# 06_-_GPIO.net
KiCad netlist of a schematic drawn in Altium Designer
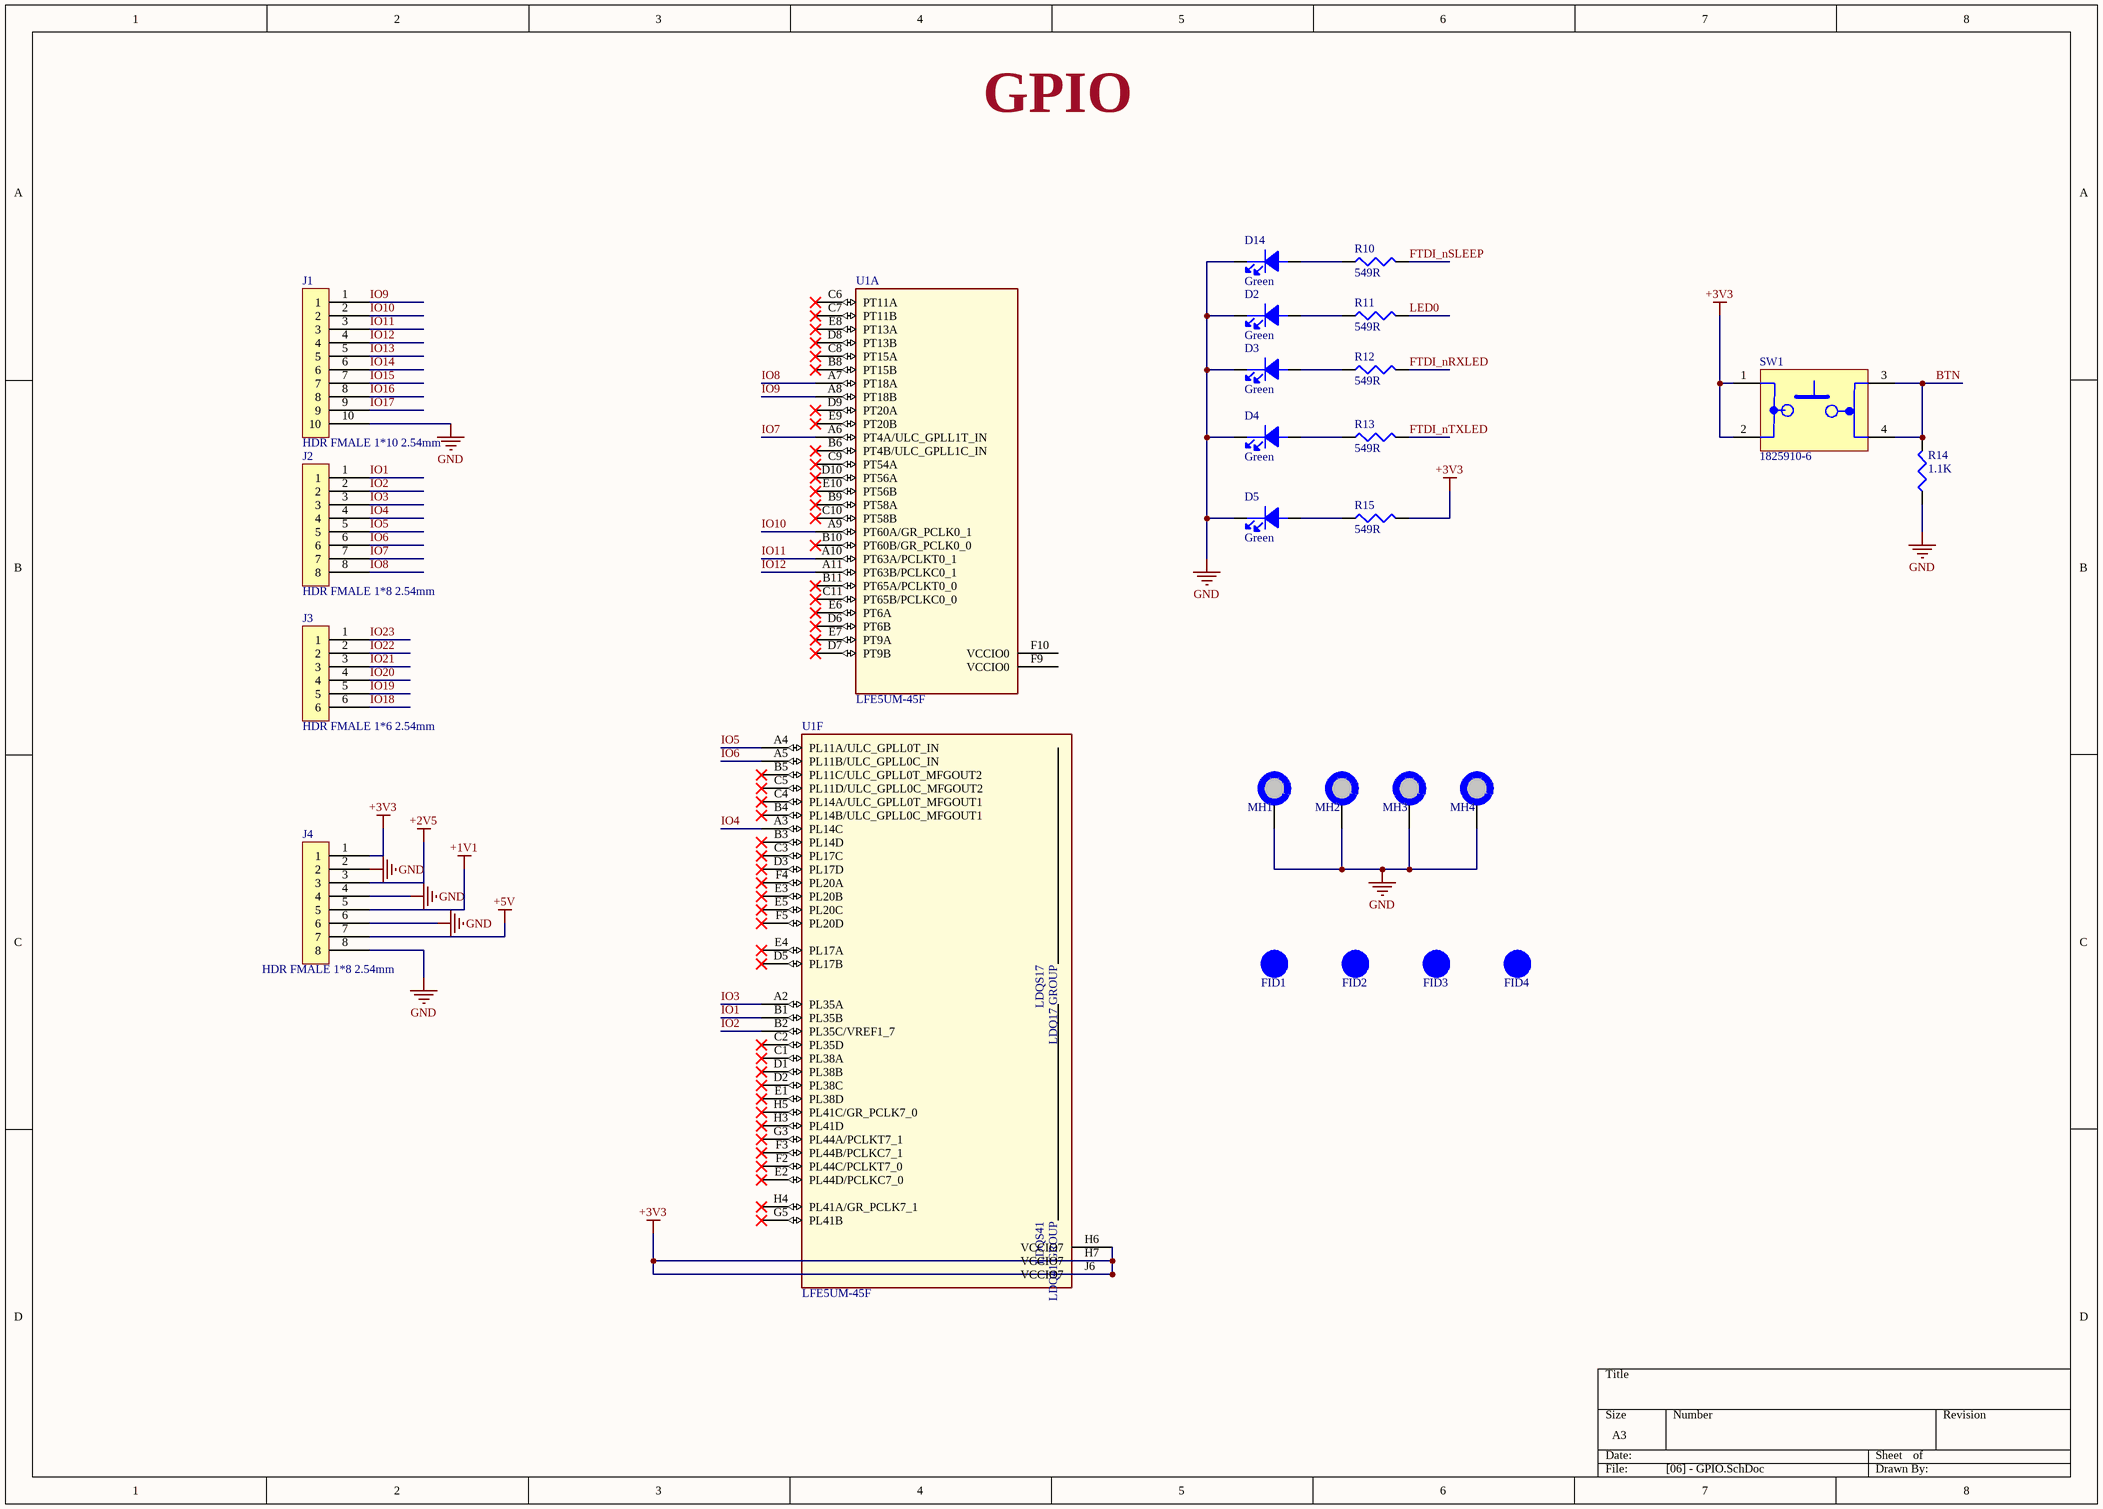
[diagram p0: [06] - GPIO.SchDoc]

(export (version "E")
  (design (tool "Eeschema 10.0.6"))
  (components
    (comp (ref "D2")
      (value "Green")
      (footprint "LED_0603")
      (description "LED Uni-Color Green 572nm 2-Pin Chip 0603(1608Metric) T/R")
      (fields
        (field (name "MANUFACTURER") "Osram Opto")
        (field (name "MANUFACTURER PART NUMBER") "LGL29K-G2J1-24-Z")
      )
      (libsource (lib "ECP5_V2") (part "LGL29K-G2J1-24-Z"))
    )
    (comp (ref "D3")
      (value "Green")
      (footprint "LED_0603")
      (description "LED Uni-Color Green 572nm 2-Pin Chip 0603(1608Metric) T/R")
      (fields
        (field (name "MANUFACTURER") "Osram Opto")
        (field (name "MANUFACTURER PART NUMBER") "LGL29K-G2J1-24-Z")
      )
      (libsource (lib "ECP5_V2") (part "LGL29K-G2J1-24-Z"))
    )
    (comp (ref "D4")
      (value "Green")
      (footprint "LED_0603")
      (description "LED Uni-Color Green 572nm 2-Pin Chip 0603(1608Metric) T/R")
      (fields
        (field (name "MANUFACTURER") "Osram Opto")
        (field (name "MANUFACTURER PART NUMBER") "LGL29K-G2J1-24-Z")
      )
      (libsource (lib "ECP5_V2") (part "LGL29K-G2J1-24-Z"))
    )
    (comp (ref "D5")
      (value "Green")
      (footprint "LED_0603")
      (description "LED Uni-Color Green 572nm 2-Pin Chip 0603(1608Metric) T/R")
      (fields
        (field (name "MANUFACTURER") "Osram Opto")
        (field (name "MANUFACTURER PART NUMBER") "LGL29K-G2J1-24-Z")
      )
      (libsource (lib "ECP5_V2") (part "LGL29K-G2J1-24-Z"))
    )
    (comp (ref "D14")
      (value "Green")
      (footprint "LED_0603")
      (description "LED Uni-Color Green 572nm 2-Pin Chip 0603(1608Metric) T/R")
      (fields
        (field (name "MANUFACTURER") "Osram Opto")
        (field (name "MANUFACTURER PART NUMBER") "LGL29K-G2J1-24-Z")
      )
      (libsource (lib "ECP5_V2") (part "LGL29K-G2J1-24-Z"))
    )
    (comp (ref "FID1")
      (value "FID_1MMC")
      (footprint "FID_40x120D")
      (description "Fiducial 40mil Diameter 120mil Mask")
      (libsource (lib "ECP5_V2") (part "FID_1MMC"))
    )
    (comp (ref "FID2")
      (value "FID_1MMC")
      (footprint "FID_40x120D")
      (description "Fiducial 40mil Diameter 120mil Mask")
      (libsource (lib "ECP5_V2") (part "FID_1MMC"))
    )
    (comp (ref "FID3")
      (value "FID_1MMC")
      (footprint "FID_40x120D")
      (description "Fiducial 40mil Diameter 120mil Mask")
      (libsource (lib "ECP5_V2") (part "FID_1MMC"))
    )
    (comp (ref "FID4")
      (value "FID_1MMC")
      (footprint "FID_40x120D")
      (description "Fiducial 40mil Diameter 120mil Mask")
      (libsource (lib "ECP5_V2") (part "FID_1MMC"))
    )
    (comp (ref "J1")
      (value "HDR FMALE 1*10 2.54mm")
      (footprint "Hdr_Female_1*10_2.54mm")
      (description "10-WAY SIL VERT SOCKET L/FREE")
      (fields (field (name "MANUFACTURER") "Harwin") (field (name "MANUFACTURER PART NUMBER") "M20-7821046"))
      (libsource (lib "ECP5_V2") (part "M20-7821046"))
    )
    (comp (ref "J2")
      (value "HDR FMALE 1*8 2.54mm")
      (footprint "Hdr_Female_1*8_2.54mm")
      (description "08-WAY SIL VERT SOCKET L/FREE")
      (fields (field (name "MANUFACTURER") "Harwin") (field (name "MANUFACTURER PART NUMBER") "M20-7820842"))
      (libsource (lib "ECP5_V2") (part "M20-7820842"))
    )
    (comp (ref "J3")
      (value "HDR FMALE 1*6 2.54mm")
      (footprint "Hdr_Female_1*6_2.54mm")
      (description "06-WAY SIL VERT SOCKET L/FREE")
      (fields (field (name "MANUFACTURER") "Harwin") (field (name "MANUFACTURER PART NUMBER") "M20-7820646"))
      (libsource (lib "ECP5_V2") (part "M20-7820646"))
    )
    (comp (ref "J4")
      (value "HDR FMALE 1*8 2.54mm")
      (footprint "Hdr_Female_1*8_2.54mm")
      (description "08-WAY SIL VERT SOCKET L/FREE")
      (fields (field (name "MANUFACTURER") "Harwin") (field (name "MANUFACTURER PART NUMBER") "M20-7820842"))
      (libsource (lib "ECP5_V2") (part "M20-7820842"))
    )
    (comp (ref "MH1")
      (value "MH_7.4MMC_3.2MMD")
      (footprint "MH_7.4MMC_3.2MMD")
      (description "Mounting Hole 7..4mm Diameter_3.2mm Drill")
      (libsource (lib "ECP5_V2") (part "MH_7.4MMC_3.2MMD"))
    )
    (comp (ref "MH2")
      (value "MH_7.4MMC_3.2MMD")
      (footprint "MH_7.4MMC_3.2MMD")
      (description "Mounting Hole 7..4mm Diameter_3.2mm Drill")
      (libsource (lib "ECP5_V2") (part "MH_7.4MMC_3.2MMD"))
    )
    (comp (ref "MH3")
      (value "MH_7.4MMC_3.2MMD")
      (footprint "MH_7.4MMC_3.2MMD")
      (description "Mounting Hole 7..4mm Diameter_3.2mm Drill")
      (libsource (lib "ECP5_V2") (part "MH_7.4MMC_3.2MMD"))
    )
    (comp (ref "MH4")
      (value "MH_7.4MMC_3.2MMD")
      (footprint "MH_7.4MMC_3.2MMD")
      (description "Mounting Hole 7..4mm Diameter_3.2mm Drill")
      (libsource (lib "ECP5_V2") (part "MH_7.4MMC_3.2MMD"))
    )
    (comp (ref "R10")
      (value "549R")
      (footprint "R0603")
      (description "RES SMD 549 OHM 1% 1/10W 0603")
      (fields
        (field (name "MANUFACTURER") "Yageo")
        (field (name "MANUFACTURER PART NUMBER") "RC0603FR-07549RL")
      )
      (libsource (lib "ECP5_V2") (part "RC0603FR-07549RL"))
    )
    (comp (ref "R11")
      (value "549R")
      (footprint "R0603")
      (description "RES SMD 549 OHM 1% 1/10W 0603")
      (fields
        (field (name "MANUFACTURER") "Yageo")
        (field (name "MANUFACTURER PART NUMBER") "RC0603FR-07549RL")
      )
      (libsource (lib "ECP5_V2") (part "RC0603FR-07549RL"))
    )
    (comp (ref "R12")
      (value "549R")
      (footprint "R0603")
      (description "RES SMD 549 OHM 1% 1/10W 0603")
      (fields
        (field (name "MANUFACTURER") "Yageo")
        (field (name "MANUFACTURER PART NUMBER") "RC0603FR-07549RL")
      )
      (libsource (lib "ECP5_V2") (part "RC0603FR-07549RL"))
    )
    (comp (ref "R13")
      (value "549R")
      (footprint "R0603")
      (description "RES SMD 549 OHM 1% 1/10W 0603")
      (fields
        (field (name "MANUFACTURER") "Yageo")
        (field (name "MANUFACTURER PART NUMBER") "RC0603FR-07549RL")
      )
      (libsource (lib "ECP5_V2") (part "RC0603FR-07549RL"))
    )
    (comp (ref "R14")
      (value "1.1K")
      (footprint "R0603")
      (description "RES SMD 1.1K OHM 1% 1/10W 0603")
      (fields
        (field (name "MANUFACTURER") "Yageo")
        (field (name "MANUFACTURER PART NUMBER") "RC0603FR-071K1L")
      )
      (libsource (lib "ECP5_V2") (part "RC0603FR-071K1L"))
    )
    (comp (ref "R15")
      (value "549R")
      (footprint "R0603")
      (description "RES SMD 549 OHM 1% 1/10W 0603")
      (fields
        (field (name "MANUFACTURER") "Yageo")
        (field (name "MANUFACTURER PART NUMBER") "RC0603FR-07549RL")
      )
      (libsource (lib "ECP5_V2") (part "RC0603FR-07549RL"))
    )
    (comp (ref "SW1")
      (value "1825910-6")
      (footprint "1825910-6")
      (description "ALCOSWITCH - TE CONNECTIVITY - 1825910-6 - TACT SWITCH, SPST, 0.05A, 24VDC, SOLDER")
      (fields (field (name "MANUFACTURER") "TE Connectivity Alcoswitch"))
      (libsource (lib "ECP5_V2") (part "1825910-6"))
    )
    (comp (ref "U1")
      (value "LFE5UM-45F")
      (footprint "LFE5BG381")
      (description "ECP5 Series 44 K LUTs 203 I/O 1.1 V Slow Surface Mount FPGA - CABGA-381")
      (fields
        (field (name "MANUFACTURER") "Lattice Semiconductor")
        (field (name "MANUFACTURER PART NUMBER") "LFE5UM-45F-6BG381C")
      )
      (libsource (lib "ECP5_V2") (part "LFE5UM-45F-6BG381C"))
    )
  )
  (nets
    (net (code "1") (name "+1V1") (class "Default")
      (node (ref "J4") (pin "5") (pinfunction "5_5") (pintype "passive"))
    )
    (net (code "2") (name "+2V5") (class "Default")
      (node (ref "J4") (pin "3") (pinfunction "3_3") (pintype "passive"))
    )
    (net (code "3") (name "+3V3") (class "Default")
      (node (ref "J4") (pin "1") (pinfunction "1_1") (pintype "passive"))
      (node (ref "R15") (pin "2") (pinfunction "2_2") (pintype "passive"))
      (node (ref "SW1") (pin "1") (pintype "passive"))
      (node (ref "SW1") (pin "2") (pintype "passive"))
      (node (ref "U1") (pin "H6") (pinfunction "VCCIO7_H6") (pintype "power_in"))
      (node (ref "U1") (pin "H7") (pinfunction "VCCIO7_H7") (pintype "power_in"))
      (node (ref "U1") (pin "J6") (pinfunction "VCCIO7_J6") (pintype "power_in"))
    )
    (net (code "4") (name "+5V") (class "Default")
      (node (ref "J4") (pin "7") (pinfunction "7_7") (pintype "passive"))
    )
    (net (code "5") (name "/BTN") (class "Default")
      (node (ref "R14") (pin "2") (pinfunction "2_2") (pintype "passive"))
      (node (ref "SW1") (pin "3") (pintype "passive"))
      (node (ref "SW1") (pin "4") (pintype "passive"))
    )
    (net (code "6") (name "/FTDI_nRXLED") (class "Default")
      (node (ref "R12") (pin "2") (pinfunction "2_2") (pintype "passive"))
    )
    (net (code "7") (name "/FTDI_nSLEEP") (class "Default")
      (node (ref "R10") (pin "2") (pinfunction "2_2") (pintype "passive"))
    )
    (net (code "8") (name "/FTDI_nTXLED") (class "Default")
      (node (ref "R13") (pin "2") (pinfunction "2_2") (pintype "passive"))
    )
    (net (code "9") (name "/IO1") (class "Default")
      (node (ref "J2") (pin "1") (pinfunction "1_1") (pintype "passive"))
      (node (ref "U1") (pin "B1") (pinfunction "PL35B_B1") (pintype "bidirectional"))
    )
    (net (code "10") (name "/IO2") (class "Default")
      (node (ref "J2") (pin "2") (pinfunction "2_2") (pintype "passive"))
      (node (ref "U1") (pin "B2") (pinfunction "PL35C/VREF1_7_B2") (pintype "bidirectional"))
    )
    (net (code "11") (name "/IO3") (class "Default")
      (node (ref "J2") (pin "3") (pinfunction "3_3") (pintype "passive"))
      (node (ref "U1") (pin "A2") (pinfunction "PL35A_A2") (pintype "bidirectional"))
    )
    (net (code "12") (name "/IO4") (class "Default")
      (node (ref "J2") (pin "4") (pinfunction "4_4") (pintype "passive"))
      (node (ref "U1") (pin "A3") (pinfunction "PL14C_A3") (pintype "bidirectional"))
    )
    (net (code "13") (name "/IO5") (class "Default")
      (node (ref "J2") (pin "5") (pinfunction "5_5") (pintype "passive"))
      (node (ref "U1") (pin "A4") (pinfunction "PL11A/ULC_GPLL0T_IN_A4") (pintype "bidirectional"))
    )
    (net (code "14") (name "/IO6") (class "Default")
      (node (ref "J2") (pin "6") (pinfunction "6_6") (pintype "passive"))
      (node (ref "U1") (pin "A5") (pinfunction "PL11B/ULC_GPLL0C_IN_A5") (pintype "bidirectional"))
    )
    (net (code "15") (name "/IO7") (class "Default")
      (node (ref "J2") (pin "7") (pinfunction "7_7") (pintype "passive"))
      (node (ref "U1") (pin "A6") (pinfunction "PT4A/ULC_GPLL1T_IN_A6") (pintype "bidirectional"))
    )
    (net (code "16") (name "/IO8") (class "Default")
      (node (ref "J2") (pin "8") (pinfunction "8_8") (pintype "passive"))
      (node (ref "U1") (pin "A7") (pinfunction "PT18A_A7") (pintype "bidirectional"))
    )
    (net (code "17") (name "/IO9") (class "Default")
      (node (ref "J1") (pin "1") (pinfunction "1_1") (pintype "passive"))
      (node (ref "U1") (pin "A8") (pinfunction "PT18B_A8") (pintype "bidirectional"))
    )
    (net (code "18") (name "/IO10") (class "Default")
      (node (ref "J1") (pin "2") (pinfunction "2_2") (pintype "passive"))
      (node (ref "U1") (pin "A9") (pinfunction "PT60A/GR_PCLK0_1_A9") (pintype "bidirectional"))
    )
    (net (code "19") (name "/IO11") (class "Default")
      (node (ref "J1") (pin "3") (pinfunction "3_3") (pintype "passive"))
      (node (ref "U1") (pin "A10") (pinfunction "PT63A/PCLKT0_1_A10") (pintype "bidirectional"))
    )
    (net (code "20") (name "/IO12") (class "Default")
      (node (ref "J1") (pin "4") (pinfunction "4_4") (pintype "passive"))
      (node (ref "U1") (pin "A11") (pinfunction "PT63B/PCLKC0_1_A11") (pintype "bidirectional"))
    )
    (net (code "21") (name "/IO13") (class "Default")
      (node (ref "J1") (pin "5") (pinfunction "5_5") (pintype "passive"))
    )
    (net (code "22") (name "/IO14") (class "Default")
      (node (ref "J1") (pin "6") (pinfunction "6_6") (pintype "passive"))
    )
    (net (code "23") (name "/IO15") (class "Default")
      (node (ref "J1") (pin "7") (pinfunction "7_7") (pintype "passive"))
    )
    (net (code "24") (name "/IO16") (class "Default")
      (node (ref "J1") (pin "8") (pinfunction "8_8") (pintype "passive"))
    )
    (net (code "25") (name "/IO17") (class "Default")
      (node (ref "J1") (pin "9") (pinfunction "9_9") (pintype "passive"))
    )
    (net (code "26") (name "/IO18") (class "Default")
      (node (ref "J3") (pin "6") (pinfunction "6_6") (pintype "passive"))
    )
    (net (code "27") (name "/IO19") (class "Default")
      (node (ref "J3") (pin "5") (pinfunction "5_5") (pintype "passive"))
    )
    (net (code "28") (name "/IO20") (class "Default")
      (node (ref "J3") (pin "4") (pinfunction "4_4") (pintype "passive"))
    )
    (net (code "29") (name "/IO21") (class "Default")
      (node (ref "J3") (pin "3") (pinfunction "3_3") (pintype "passive"))
    )
    (net (code "30") (name "/IO22") (class "Default")
      (node (ref "J3") (pin "2") (pinfunction "2_2") (pintype "passive"))
    )
    (net (code "31") (name "/IO23") (class "Default")
      (node (ref "J3") (pin "1") (pinfunction "1_1") (pintype "passive"))
    )
    (net (code "32") (name "/LED0") (class "Default")
      (node (ref "R11") (pin "2") (pinfunction "2_2") (pintype "passive"))
    )
    (net (code "33") (name "GND") (class "Default")
      (node (ref "D14") (pin "1") (pinfunction "Cathode_1") (pintype "passive"))
      (node (ref "D2") (pin "1") (pinfunction "Cathode_1") (pintype "passive"))
      (node (ref "D3") (pin "1") (pinfunction "Cathode_1") (pintype "passive"))
      (node (ref "D4") (pin "1") (pinfunction "Cathode_1") (pintype "passive"))
      (node (ref "D5") (pin "1") (pinfunction "Cathode_1") (pintype "passive"))
      (node (ref "J1") (pin "10") (pinfunction "10_10") (pintype "passive"))
      (node (ref "J4") (pin "2") (pinfunction "2_2") (pintype "passive"))
      (node (ref "J4") (pin "4") (pinfunction "4_4") (pintype "passive"))
      (node (ref "J4") (pin "6") (pinfunction "6_6") (pintype "passive"))
      (node (ref "J4") (pin "8") (pinfunction "8_8") (pintype "passive"))
      (node (ref "MH1") (pin "1") (pinfunction "1_1") (pintype "passive"))
      (node (ref "MH2") (pin "1") (pinfunction "1_1") (pintype "passive"))
      (node (ref "MH3") (pin "1") (pinfunction "1_1") (pintype "passive"))
      (node (ref "MH4") (pin "1") (pinfunction "1_1") (pintype "passive"))
      (node (ref "R14") (pin "1") (pinfunction "1_1") (pintype "passive"))
    )
    (net (code "34") (name "Net-(D2-Anode)") (class "Default")
      (node (ref "D2") (pin "2") (pinfunction "Anode_2") (pintype "passive"))
      (node (ref "R11") (pin "1") (pinfunction "1_1") (pintype "passive"))
    )
    (net (code "35") (name "Net-(D3-Anode)") (class "Default")
      (node (ref "D3") (pin "2") (pinfunction "Anode_2") (pintype "passive"))
      (node (ref "R12") (pin "1") (pinfunction "1_1") (pintype "passive"))
    )
    (net (code "36") (name "Net-(D4-Anode)") (class "Default")
      (node (ref "D4") (pin "2") (pinfunction "Anode_2") (pintype "passive"))
      (node (ref "R13") (pin "1") (pinfunction "1_1") (pintype "passive"))
    )
    (net (code "37") (name "Net-(D5-Anode)") (class "Default")
      (node (ref "D5") (pin "2") (pinfunction "Anode_2") (pintype "passive"))
      (node (ref "R15") (pin "1") (pinfunction "1_1") (pintype "passive"))
    )
    (net (code "38") (name "Net-(D14-Anode)") (class "Default")
      (node (ref "D14") (pin "2") (pinfunction "Anode_2") (pintype "passive"))
      (node (ref "R10") (pin "1") (pinfunction "1_1") (pintype "passive"))
    )
    (net (code "39") (name "unconnected-(U1A-PT4B{slash}ULC_GPLL1C_IN-PadB6)") (class "Default")
      (node (ref "U1") (pin "B6") (pinfunction "PT4B/ULC_GPLL1C_IN_B6") (pintype "bidirectional+no_connect"))
    )
    (net (code "40") (name "unconnected-(U1A-PT6A-PadE6)") (class "Default")
      (node (ref "U1") (pin "E6") (pinfunction "PT6A_E6") (pintype "bidirectional+no_connect"))
    )
    (net (code "41") (name "unconnected-(U1A-PT6B-PadD6)") (class "Default")
      (node (ref "U1") (pin "D6") (pinfunction "PT6B_D6") (pintype "bidirectional+no_connect"))
    )
    (net (code "42") (name "unconnected-(U1A-PT9A-PadE7)") (class "Default")
      (node (ref "U1") (pin "E7") (pinfunction "PT9A_E7") (pintype "bidirectional+no_connect"))
    )
    (net (code "43") (name "unconnected-(U1A-PT9B-PadD7)") (class "Default")
      (node (ref "U1") (pin "D7") (pinfunction "PT9B_D7") (pintype "bidirectional+no_connect"))
    )
    (net (code "44") (name "unconnected-(U1A-PT11A-PadC6)") (class "Default")
      (node (ref "U1") (pin "C6") (pinfunction "PT11A_C6") (pintype "bidirectional+no_connect"))
    )
    (net (code "45") (name "unconnected-(U1A-PT11B-PadC7)") (class "Default")
      (node (ref "U1") (pin "C7") (pinfunction "PT11B_C7") (pintype "bidirectional+no_connect"))
    )
    (net (code "46") (name "unconnected-(U1A-PT13A-PadE8)") (class "Default")
      (node (ref "U1") (pin "E8") (pinfunction "PT13A_E8") (pintype "bidirectional+no_connect"))
    )
    (net (code "47") (name "unconnected-(U1A-PT13B-PadD8)") (class "Default")
      (node (ref "U1") (pin "D8") (pinfunction "PT13B_D8") (pintype "bidirectional+no_connect"))
    )
    (net (code "48") (name "unconnected-(U1A-PT15A-PadC8)") (class "Default")
      (node (ref "U1") (pin "C8") (pinfunction "PT15A_C8") (pintype "bidirectional+no_connect"))
    )
    (net (code "49") (name "unconnected-(U1A-PT15B-PadB8)") (class "Default")
      (node (ref "U1") (pin "B8") (pinfunction "PT15B_B8") (pintype "bidirectional+no_connect"))
    )
    (net (code "50") (name "unconnected-(U1A-PT20A-PadD9)") (class "Default")
      (node (ref "U1") (pin "D9") (pinfunction "PT20A_D9") (pintype "bidirectional+no_connect"))
    )
    (net (code "51") (name "unconnected-(U1A-PT20B-PadE9)") (class "Default")
      (node (ref "U1") (pin "E9") (pinfunction "PT20B_E9") (pintype "bidirectional+no_connect"))
    )
    (net (code "52") (name "unconnected-(U1A-PT54A-PadC9)") (class "Default")
      (node (ref "U1") (pin "C9") (pinfunction "PT54A_C9") (pintype "bidirectional+no_connect"))
    )
    (net (code "53") (name "unconnected-(U1A-PT56A-PadD10)") (class "Default")
      (node (ref "U1") (pin "D10") (pinfunction "PT56A_D10") (pintype "bidirectional+no_connect"))
    )
    (net (code "54") (name "unconnected-(U1A-PT56B-PadE10)") (class "Default")
      (node (ref "U1") (pin "E10") (pinfunction "PT56B_E10") (pintype "bidirectional+no_connect"))
    )
    (net (code "55") (name "unconnected-(U1A-PT58A-PadB9)") (class "Default")
      (node (ref "U1") (pin "B9") (pinfunction "PT58A_B9") (pintype "bidirectional+no_connect"))
    )
    (net (code "56") (name "unconnected-(U1A-PT58B-PadC10)") (class "Default")
      (node (ref "U1") (pin "C10") (pinfunction "PT58B_C10") (pintype "bidirectional+no_connect"))
    )
    (net (code "57") (name "unconnected-(U1A-PT60B{slash}GR_PCLK0_0-PadB10)") (class "Default")
      (node (ref "U1") (pin "B10") (pinfunction "PT60B/GR_PCLK0_0_B10") (pintype "bidirectional+no_connect"))
    )
    (net (code "58") (name "unconnected-(U1A-PT65A{slash}PCLKT0_0-PadB11)") (class "Default")
      (node (ref "U1") (pin "B11") (pinfunction "PT65A/PCLKT0_0_B11") (pintype "bidirectional+no_connect"))
    )
    (net (code "59") (name "unconnected-(U1A-PT65B{slash}PCLKC0_0-PadC11)") (class "Default")
      (node (ref "U1") (pin "C11") (pinfunction "PT65B/PCLKC0_0_C11") (pintype "bidirectional+no_connect"))
    )
    (net (code "60") (name "unconnected-(U1A-VCCIO0-PadF9)") (class "Default")
      (node (ref "U1") (pin "F9") (pinfunction "VCCIO0_F9") (pintype "power_in"))
    )
    (net (code "61") (name "unconnected-(U1A-VCCIO0-PadF10)") (class "Default")
      (node (ref "U1") (pin "F10") (pinfunction "VCCIO0_F10") (pintype "power_in"))
    )
    (net (code "62") (name "unconnected-(U1F-PL11C{slash}ULC_GPLL0T_MFGOUT2-PadB5)") (class "Default")
      (node (ref "U1") (pin "B5") (pinfunction "PL11C/ULC_GPLL0T_MFGOUT2_B5") (pintype "bidirectional+no_connect"))
    )
    (net (code "63") (name "unconnected-(U1F-PL11D{slash}ULC_GPLL0C_MFGOUT2-PadC5)") (class "Default")
      (node (ref "U1") (pin "C5") (pinfunction "PL11D/ULC_GPLL0C_MFGOUT2_C5") (pintype "bidirectional+no_connect"))
    )
    (net (code "64") (name "unconnected-(U1F-PL14A{slash}ULC_GPLL0T_MFGOUT1-PadC4)") (class "Default")
      (node (ref "U1") (pin "C4") (pinfunction "PL14A/ULC_GPLL0T_MFGOUT1_C4") (pintype "bidirectional+no_connect"))
    )
    (net (code "65") (name "unconnected-(U1F-PL14B{slash}ULC_GPLL0C_MFGOUT1-PadB4)") (class "Default")
      (node (ref "U1") (pin "B4") (pinfunction "PL14B/ULC_GPLL0C_MFGOUT1_B4") (pintype "bidirectional+no_connect"))
    )
    (net (code "66") (name "unconnected-(U1F-PL14D-PadB3)") (class "Default")
      (node (ref "U1") (pin "B3") (pinfunction "PL14D_B3") (pintype "bidirectional+no_connect"))
    )
    (net (code "67") (name "unconnected-(U1F-PL17A-PadE4)") (class "Default")
      (node (ref "U1") (pin "E4") (pinfunction "PL17A_E4") (pintype "bidirectional+no_connect"))
    )
    (net (code "68") (name "unconnected-(U1F-PL17B-PadD5)") (class "Default")
      (node (ref "U1") (pin "D5") (pinfunction "PL17B_D5") (pintype "bidirectional+no_connect"))
    )
    (net (code "69") (name "unconnected-(U1F-PL17C-PadC3)") (class "Default")
      (node (ref "U1") (pin "C3") (pinfunction "PL17C_C3") (pintype "bidirectional+no_connect"))
    )
    (net (code "70") (name "unconnected-(U1F-PL17D-PadD3)") (class "Default")
      (node (ref "U1") (pin "D3") (pinfunction "PL17D_D3") (pintype "bidirectional+no_connect"))
    )
    (net (code "71") (name "unconnected-(U1F-PL20A-PadF4)") (class "Default")
      (node (ref "U1") (pin "F4") (pinfunction "PL20A_F4") (pintype "bidirectional+no_connect"))
    )
    (net (code "72") (name "unconnected-(U1F-PL20B-PadE3)") (class "Default")
      (node (ref "U1") (pin "E3") (pinfunction "PL20B_E3") (pintype "bidirectional+no_connect"))
    )
    (net (code "73") (name "unconnected-(U1F-PL20C-PadE5)") (class "Default")
      (node (ref "U1") (pin "E5") (pinfunction "PL20C_E5") (pintype "bidirectional+no_connect"))
    )
    (net (code "74") (name "unconnected-(U1F-PL20D-PadF5)") (class "Default")
      (node (ref "U1") (pin "F5") (pinfunction "PL20D_F5") (pintype "bidirectional+no_connect"))
    )
    (net (code "75") (name "unconnected-(U1F-PL35D-PadC2)") (class "Default")
      (node (ref "U1") (pin "C2") (pinfunction "PL35D_C2") (pintype "bidirectional+no_connect"))
    )
    (net (code "76") (name "unconnected-(U1F-PL38A-PadC1)") (class "Default")
      (node (ref "U1") (pin "C1") (pinfunction "PL38A_C1") (pintype "bidirectional+no_connect"))
    )
    (net (code "77") (name "unconnected-(U1F-PL38B-PadD1)") (class "Default")
      (node (ref "U1") (pin "D1") (pinfunction "PL38B_D1") (pintype "bidirectional+no_connect"))
    )
    (net (code "78") (name "unconnected-(U1F-PL38C-PadD2)") (class "Default")
      (node (ref "U1") (pin "D2") (pinfunction "PL38C_D2") (pintype "bidirectional+no_connect"))
    )
    (net (code "79") (name "unconnected-(U1F-PL38D-PadE1)") (class "Default")
      (node (ref "U1") (pin "E1") (pinfunction "PL38D_E1") (pintype "bidirectional+no_connect"))
    )
    (net (code "80") (name "unconnected-(U1F-PL41A{slash}GR_PCLK7_1-PadH4)") (class "Default")
      (node (ref "U1") (pin "H4") (pinfunction "PL41A/GR_PCLK7_1_H4") (pintype "bidirectional+no_connect"))
    )
    (net (code "81") (name "unconnected-(U1F-PL41B-PadG5)") (class "Default")
      (node (ref "U1") (pin "G5") (pinfunction "PL41B_G5") (pintype "bidirectional+no_connect"))
    )
    (net (code "82") (name "unconnected-(U1F-PL41C{slash}GR_PCLK7_0-PadH5)") (class "Default")
      (node (ref "U1") (pin "H5") (pinfunction "PL41C/GR_PCLK7_0_H5") (pintype "bidirectional+no_connect"))
    )
    (net (code "83") (name "unconnected-(U1F-PL41D-PadH3)") (class "Default")
      (node (ref "U1") (pin "H3") (pinfunction "PL41D_H3") (pintype "bidirectional+no_connect"))
    )
    (net (code "84") (name "unconnected-(U1F-PL44A{slash}PCLKT7_1-PadG3)") (class "Default")
      (node (ref "U1") (pin "G3") (pinfunction "PL44A/PCLKT7_1_G3") (pintype "bidirectional+no_connect"))
    )
    (net (code "85") (name "unconnected-(U1F-PL44B{slash}PCLKC7_1-PadF3)") (class "Default")
      (node (ref "U1") (pin "F3") (pinfunction "PL44B/PCLKC7_1_F3") (pintype "bidirectional+no_connect"))
    )
    (net (code "86") (name "unconnected-(U1F-PL44C{slash}PCLKT7_0-PadF2)") (class "Default")
      (node (ref "U1") (pin "F2") (pinfunction "PL44C/PCLKT7_0_F2") (pintype "bidirectional+no_connect"))
    )
    (net (code "87") (name "unconnected-(U1F-PL44D{slash}PCLKC7_0-PadE2)") (class "Default")
      (node (ref "U1") (pin "E2") (pinfunction "PL44D/PCLKC7_0_E2") (pintype "bidirectional+no_connect"))
    )
  )
)
